# Main_Controller.net
KiCad netlist of a schematic drawn in Altium Designer
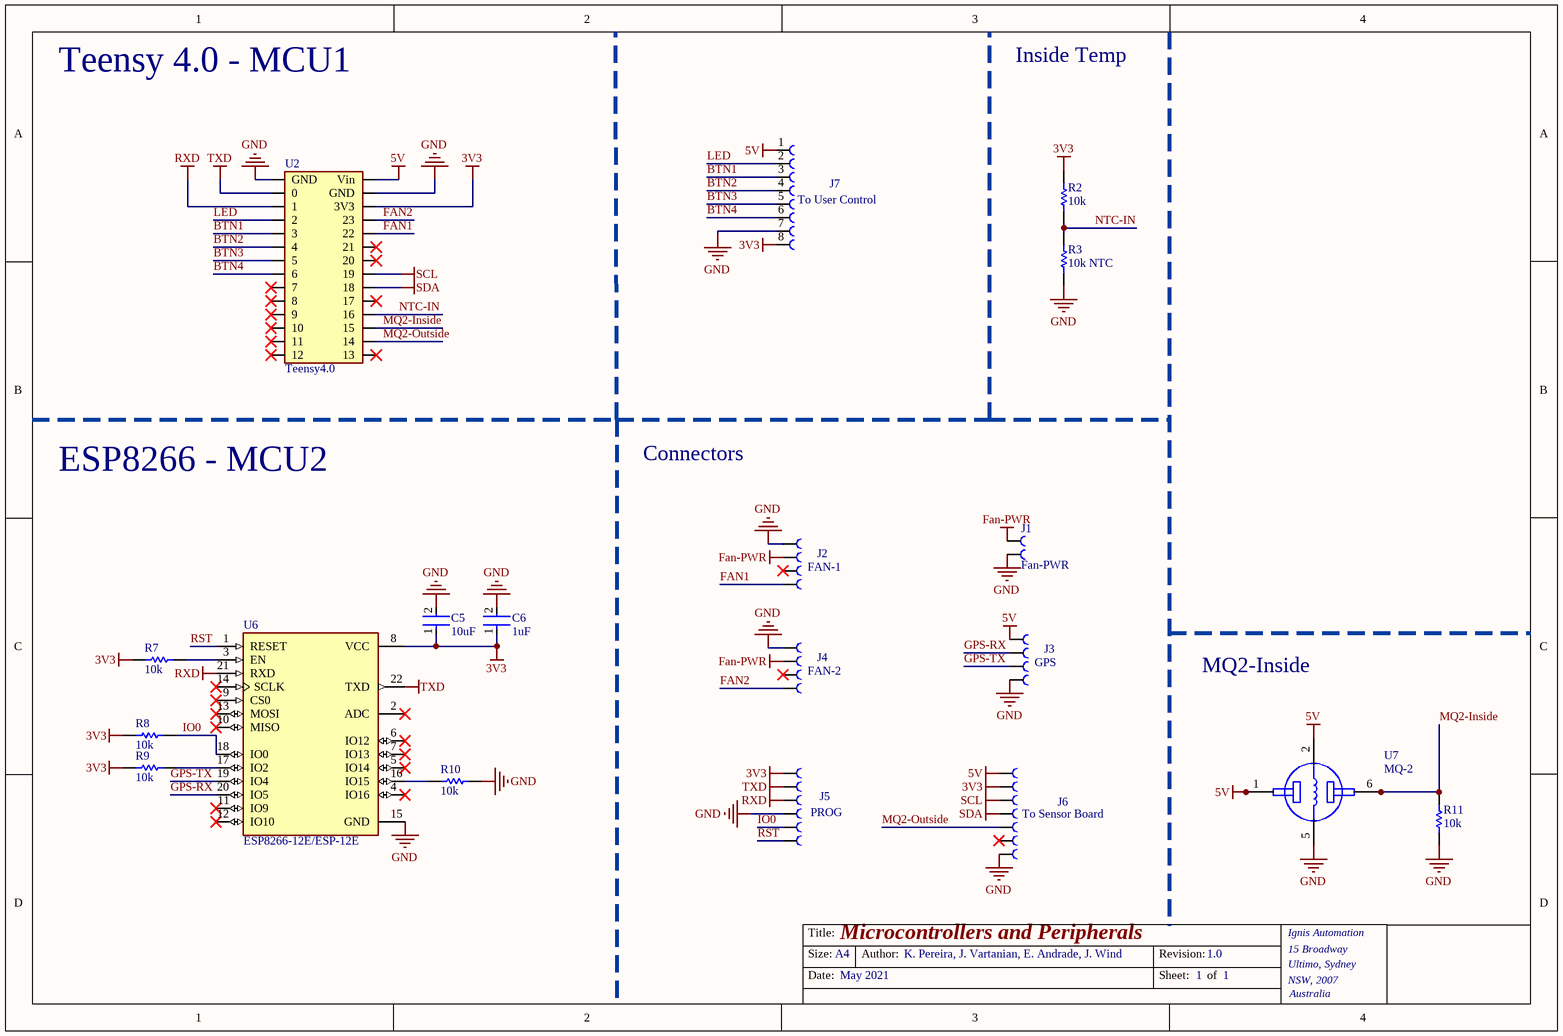
[diagram p0: Main Controller.SchDoc]

(export (version "E")
  (design (tool "Eeschema 10.0.6"))
  (components
    (comp (ref "C5")
      (value "10uF")
      (footprint "FP-CL10-IPC_C")
      (description "CAP CER 10UF 16V X5R 0603")
      (fields (field (name "PART NUMBER") "587-3238-1-ND"))
      (libsource (lib "Altium Content Vault") (part "b4654b650e69147ec39a6b967a45e02"))
    )
    (comp (ref "C6")
      (value "1uF")
      (footprint "FP-CL10-IPC_C")
      (description "CAP CER 1UF 25V X5R 0603")
      (fields (field (name "PART NUMBER") "1276-1102-1-ND"))
      (libsource (lib "Altium Content Vault") (part "b4654b650e69147ec39a6b967a45e02"))
    )
    (comp (ref "J1")
      (value "Fan-PWR")
      (footprint "2pin:61300711821")
      (description "2 Pin")
      (libsource (lib "2pin") (part "61300711821"))
    )
    (comp (ref "J2")
      (value "FAN-1")
      (footprint "4pin:61300711821")
      (description "4 Pin")
      (libsource (lib "4pin") (part "61300711821"))
    )
    (comp (ref "J3")
      (value "GPS")
      (footprint "4pin:61300711821")
      (description "4 Pin")
      (libsource (lib "4pin") (part "61300711821"))
    )
    (comp (ref "J4")
      (value "FAN-2")
      (footprint "4pin:61300711821")
      (description "4 Pin")
      (libsource (lib "4pin") (part "61300711821"))
    )
    (comp (ref "J5")
      (value "PROG")
      (footprint "6pin:61300711821")
      (description "6 Pin")
      (libsource (lib "6pin") (part "61300711821"))
    )
    (comp (ref "J6")
      (value "To Sensor Board")
      (footprint "7pin:61300711821")
      (description "7 Pin")
      (libsource (lib "7pin") (part "61300711821"))
    )
    (comp (ref "J7")
      (value "To User Control")
      (footprint "8pin:61300711821")
      (description "8 Pin")
      (fields (field (name "MF") "WÃ¼rth Elektronik") (field (name "MP") "61300711821"))
      (libsource (lib "8pin") (part "61300711821"))
    )
    (comp (ref "R2")
      (value "10k")
      (footprint "RESC1608X55X30NL15T15")
      (description "RES SMD 10K OHM 1% 1/10W 0603")
      (fields (field (name "PART NUMBER") "A121523CT-ND"))
      (libsource (lib "Altium Content Vault") (part "RES"))
    )
    (comp (ref "R3")
      (value "10k NTC")
      (footprint "RESC1608X55X30NL15T15")
      (description "THERMISTOR NTC 10KOHM 4250K 0603")
      (fields (field (name "PART NUMBER") "P10547CT-ND"))
      (libsource (lib "Altium Content Vault") (part "RES"))
    )
    (comp (ref "R7")
      (value "10k")
      (footprint "RESC1608X55X30NL15T15")
      (description "RES SMD 10K OHM 1% 1/10W 0603")
      (fields (field (name "PART NUMBER") "A121523CT-ND"))
      (libsource (lib "Altium Content Vault") (part "RES"))
    )
    (comp (ref "R8")
      (value "10k")
      (footprint "RESC1608X55X30NL15T15")
      (description "RES SMD 10K OHM 1% 1/10W 0603")
      (fields (field (name "PART NUMBER") "A121523CT-ND"))
      (libsource (lib "Altium Content Vault") (part "RES"))
    )
    (comp (ref "R9")
      (value "10k")
      (footprint "RESC1608X55X30NL15T15")
      (description "RES SMD 10K OHM 1% 1/10W 0603")
      (fields (field (name "PART NUMBER") "A121523CT-ND"))
      (libsource (lib "Altium Content Vault") (part "RES"))
    )
    (comp (ref "R10")
      (value "10k")
      (footprint "RESC1608X55X30NL15T15")
      (description "RES SMD 10K OHM 1% 1/10W 0603")
      (fields (field (name "PART NUMBER") "A121523CT-ND"))
      (libsource (lib "Altium Content Vault") (part "RES"))
    )
    (comp (ref "R11")
      (value "10k")
      (footprint "RESC1608X55X30NL15T15")
      (description "RES SMD 10K OHM 1% 1/10W 0603")
      (fields (field (name "PART NUMBER") "A121523CT-ND"))
      (libsource (lib "Altium Content Vault") (part "RES"))
    )
    (comp (ref "U2")
      (value "Teensy4.0")
      (footprint "Teensy4.0:61301411821")
      (libsource (lib "Teensy4.0") (part "Teensy4.0"))
    )
    (comp (ref "U6")
      (value "ESP8266-12E/ESP-12E")
      (footprint "ESP8266:XCVR_ESP8266-12E/ESP-12E")
      (description "RX TXRX MOD WIFI TRACE ANT SMD")
      (fields (field (name "PART NUMBER") "1528-1438-ND"))
      (libsource (lib "ESP8266") (part "ESP8266-12E/ESP-12E"))
    )
    (comp (ref "U7")
      (value "MQ-2")
      (footprint "MQ-2:XDCR_SEN-08880")
      (description "MQ-2 Gas Sensor")
      (libsource (lib "MQ-2") (part "MQ-2"))
    )
  )
  (nets
    (net (code "1") (name "/BTN1") (class "Default")
      (node (ref "J7") (pin "3") (pinfunction "3_3") (pintype "passive"))
      (node (ref "U2") (pin "5") (pinfunction "3_5") (pintype "passive"))
    )
    (net (code "2") (name "/BTN2") (class "Default")
      (node (ref "J7") (pin "4") (pinfunction "4_4") (pintype "passive"))
      (node (ref "U2") (pin "6") (pinfunction "4_6") (pintype "passive"))
    )
    (net (code "3") (name "/BTN3") (class "Default")
      (node (ref "J7") (pin "5") (pinfunction "5_5") (pintype "passive"))
      (node (ref "U2") (pin "7") (pinfunction "5_7") (pintype "passive"))
    )
    (net (code "4") (name "/BTN4") (class "Default")
      (node (ref "J7") (pin "6") (pinfunction "6_6") (pintype "passive"))
      (node (ref "U2") (pin "8") (pinfunction "6_8") (pintype "passive"))
    )
    (net (code "5") (name "/FAN1") (class "Default")
      (node (ref "J2") (pin "4") (pinfunction "4_4") (pintype "passive"))
      (node (ref "U2") (pin "24") (pinfunction "22_24") (pintype "passive"))
    )
    (net (code "6") (name "/FAN2") (class "Default")
      (node (ref "J4") (pin "4") (pinfunction "4_4") (pintype "passive"))
      (node (ref "U2") (pin "25") (pinfunction "23_25") (pintype "passive"))
    )
    (net (code "7") (name "/GPS-RX") (class "Default")
      (node (ref "J3") (pin "2") (pinfunction "2_2") (pintype "passive"))
      (node (ref "U6") (pin "20") (pinfunction "IO5_20") (pintype "bidirectional"))
    )
    (net (code "8") (name "/GPS-TX") (class "Default")
      (node (ref "J3") (pin "3") (pinfunction "3_3") (pintype "passive"))
      (node (ref "U6") (pin "19") (pinfunction "IO4_19") (pintype "bidirectional"))
    )
    (net (code "9") (name "/IO0") (class "Default")
      (node (ref "J5") (pin "5") (pinfunction "5_5") (pintype "passive"))
      (node (ref "R8") (pin "2") (pinfunction "2_2") (pintype "passive"))
      (node (ref "U6") (pin "18") (pinfunction "IO0_18") (pintype "bidirectional"))
    )
    (net (code "10") (name "/LED") (class "Default")
      (node (ref "J7") (pin "2") (pinfunction "2_2") (pintype "passive"))
      (node (ref "U2") (pin "4") (pinfunction "2_4") (pintype "passive"))
    )
    (net (code "11") (name "/MQ2-Inside") (class "Default")
      (node (ref "R11") (pin "2") (pinfunction "2_2") (pintype "passive"))
      (node (ref "U2") (pin "17") (pinfunction "15_17") (pintype "passive"))
      (node (ref "U7") (pin "4") (pinfunction "B_4") (pintype "passive"))
      (node (ref "U7") (pin "6") (pinfunction "B_6") (pintype "passive"))
    )
    (net (code "12") (name "/MQ2-Outside") (class "Default")
      (node (ref "J6") (pin "5") (pinfunction "5_5") (pintype "passive"))
      (node (ref "U2") (pin "16") (pinfunction "14_16") (pintype "passive"))
    )
    (net (code "13") (name "/NTC-IN") (class "Default")
      (node (ref "R2") (pin "1") (pinfunction "1_1") (pintype "passive"))
      (node (ref "R3") (pin "2") (pinfunction "2_2") (pintype "passive"))
      (node (ref "U2") (pin "18") (pinfunction "16_18") (pintype "passive"))
    )
    (net (code "14") (name "/RST") (class "Default")
      (node (ref "J5") (pin "6") (pinfunction "6_6") (pintype "passive"))
      (node (ref "U6") (pin "1") (pinfunction "RESET_1") (pintype "input"))
    )
    (net (code "15") (name "3V3") (class "Default")
      (node (ref "C5") (pin "1") (pinfunction "1_1") (pintype "passive"))
      (node (ref "C6") (pin "1") (pinfunction "1_1") (pintype "passive"))
      (node (ref "J5") (pin "1") (pinfunction "1_1") (pintype "passive"))
      (node (ref "J6") (pin "2") (pinfunction "2_2") (pintype "passive"))
      (node (ref "J7") (pin "8") (pinfunction "8_8") (pintype "passive"))
      (node (ref "R2") (pin "2") (pinfunction "2_2") (pintype "passive"))
      (node (ref "R7") (pin "1") (pinfunction "1_1") (pintype "passive"))
      (node (ref "R8") (pin "1") (pinfunction "1_1") (pintype "passive"))
      (node (ref "R9") (pin "1") (pinfunction "1_1") (pintype "passive"))
      (node (ref "U2") (pin "26") (pinfunction "3V3_26") (pintype "passive"))
      (node (ref "U6") (pin "8") (pinfunction "VCC_8") (pintype "power_in"))
    )
    (net (code "16") (name "5V") (class "Default")
      (node (ref "J3") (pin "1") (pinfunction "1_1") (pintype "passive"))
      (node (ref "J6") (pin "1") (pinfunction "1_1") (pintype "passive"))
      (node (ref "J7") (pin "1") (pinfunction "1_1") (pintype "passive"))
      (node (ref "U2") (pin "28") (pinfunction "Vin_28") (pintype "passive"))
      (node (ref "U7") (pin "1") (pinfunction "A_1") (pintype "passive"))
      (node (ref "U7") (pin "2") (pinfunction "H1_2") (pintype "passive"))
      (node (ref "U7") (pin "3") (pinfunction "A_3") (pintype "passive"))
    )
    (net (code "17") (name "Fan-PWR") (class "Default")
      (node (ref "J1") (pin "2") (pinfunction "2_2") (pintype "passive"))
      (node (ref "J2") (pin "2") (pinfunction "2_2") (pintype "passive"))
      (node (ref "J4") (pin "2") (pinfunction "2_2") (pintype "passive"))
    )
    (net (code "18") (name "GND") (class "Default")
      (node (ref "C5") (pin "2") (pinfunction "2_2") (pintype "passive"))
      (node (ref "C6") (pin "2") (pinfunction "2_2") (pintype "passive"))
      (node (ref "J1") (pin "1") (pinfunction "1_1") (pintype "passive"))
      (node (ref "J2") (pin "1") (pinfunction "1_1") (pintype "passive"))
      (node (ref "J3") (pin "4") (pinfunction "4_4") (pintype "passive"))
      (node (ref "J4") (pin "1") (pinfunction "1_1") (pintype "passive"))
      (node (ref "J5") (pin "4") (pinfunction "4_4") (pintype "passive"))
      (node (ref "J6") (pin "7") (pinfunction "7_7") (pintype "passive"))
      (node (ref "J7") (pin "7") (pinfunction "7_7") (pintype "passive"))
      (node (ref "R10") (pin "2") (pinfunction "2_2") (pintype "passive"))
      (node (ref "R11") (pin "1") (pinfunction "1_1") (pintype "passive"))
      (node (ref "R3") (pin "1") (pinfunction "1_1") (pintype "passive"))
      (node (ref "U2") (pin "1") (pinfunction "GND_1") (pintype "passive"))
      (node (ref "U2") (pin "27") (pinfunction "GND_27") (pintype "passive"))
      (node (ref "U6") (pin "15") (pinfunction "GND_15") (pintype "power_in"))
      (node (ref "U7") (pin "5") (pinfunction "H2_5") (pintype "passive"))
    )
    (net (code "19") (name "Net-(U6-EN)") (class "Default")
      (node (ref "R7") (pin "2") (pinfunction "2_2") (pintype "passive"))
      (node (ref "U6") (pin "3") (pinfunction "EN_3") (pintype "input"))
    )
    (net (code "20") (name "Net-(U6-IO2)") (class "Default")
      (node (ref "R9") (pin "2") (pinfunction "2_2") (pintype "passive"))
      (node (ref "U6") (pin "17") (pinfunction "IO2_17") (pintype "bidirectional"))
    )
    (net (code "21") (name "Net-(U6-IO15)") (class "Default")
      (node (ref "R10") (pin "1") (pinfunction "1_1") (pintype "passive"))
      (node (ref "U6") (pin "16") (pinfunction "IO15_16") (pintype "bidirectional"))
    )
    (net (code "22") (name "RXD") (class "Default")
      (node (ref "J5") (pin "3") (pinfunction "3_3") (pintype "passive"))
      (node (ref "U2") (pin "3") (pinfunction "1_3") (pintype "passive"))
      (node (ref "U6") (pin "21") (pinfunction "RXD_21") (pintype "input"))
    )
    (net (code "23") (name "SCL") (class "Default")
      (node (ref "J6") (pin "3") (pinfunction "3_3") (pintype "passive"))
      (node (ref "U2") (pin "21") (pinfunction "19_21") (pintype "passive"))
    )
    (net (code "24") (name "SDA") (class "Default")
      (node (ref "J6") (pin "4") (pinfunction "4_4") (pintype "passive"))
      (node (ref "U2") (pin "20") (pinfunction "18_20") (pintype "passive"))
    )
    (net (code "25") (name "TXD") (class "Default")
      (node (ref "J5") (pin "2") (pinfunction "2_2") (pintype "passive"))
      (node (ref "U2") (pin "2") (pinfunction "0_2") (pintype "passive"))
      (node (ref "U6") (pin "22") (pinfunction "TXD_22") (pintype "output"))
    )
    (net (code "26") (name "unconnected-(J2-Pad3)") (class "Default")
      (node (ref "J2") (pin "3") (pinfunction "3_3") (pintype "passive+no_connect"))
    )
    (net (code "27") (name "unconnected-(J4-Pad3)") (class "Default")
      (node (ref "J4") (pin "3") (pinfunction "3_3") (pintype "passive+no_connect"))
    )
    (net (code "28") (name "unconnected-(J6-Pad6)") (class "Default")
      (node (ref "J6") (pin "6") (pinfunction "6_6") (pintype "passive+no_connect"))
    )
    (net (code "29") (name "unconnected-(U2-7-Pad9)") (class "Default")
      (node (ref "U2") (pin "9") (pinfunction "7_9") (pintype "passive+no_connect"))
    )
    (net (code "30") (name "unconnected-(U2-8-Pad10)") (class "Default")
      (node (ref "U2") (pin "10") (pinfunction "8_10") (pintype "passive+no_connect"))
    )
    (net (code "31") (name "unconnected-(U2-9-Pad11)") (class "Default")
      (node (ref "U2") (pin "11") (pinfunction "9_11") (pintype "passive+no_connect"))
    )
    (net (code "32") (name "unconnected-(U2-10-Pad12)") (class "Default")
      (node (ref "U2") (pin "12") (pinfunction "10_12") (pintype "passive+no_connect"))
    )
    (net (code "33") (name "unconnected-(U2-11-Pad13)") (class "Default")
      (node (ref "U2") (pin "13") (pinfunction "11_13") (pintype "passive+no_connect"))
    )
    (net (code "34") (name "unconnected-(U2-12-Pad14)") (class "Default")
      (node (ref "U2") (pin "14") (pinfunction "12_14") (pintype "passive+no_connect"))
    )
    (net (code "35") (name "unconnected-(U2-13-Pad15)") (class "Default")
      (node (ref "U2") (pin "15") (pinfunction "13_15") (pintype "passive+no_connect"))
    )
    (net (code "36") (name "unconnected-(U2-17-Pad19)") (class "Default")
      (node (ref "U2") (pin "19") (pinfunction "17_19") (pintype "passive+no_connect"))
    )
    (net (code "37") (name "unconnected-(U2-20-Pad22)") (class "Default")
      (node (ref "U2") (pin "22") (pinfunction "20_22") (pintype "passive+no_connect"))
    )
    (net (code "38") (name "unconnected-(U2-21-Pad23)") (class "Default")
      (node (ref "U2") (pin "23") (pinfunction "21_23") (pintype "passive+no_connect"))
    )
    (net (code "39") (name "unconnected-(U6-ADC-Pad2)") (class "Default")
      (node (ref "U6") (pin "2") (pinfunction "ADC_2") (pintype "passive+no_connect"))
    )
    (net (code "40") (name "unconnected-(U6-CS0-Pad9)") (class "Default")
      (node (ref "U6") (pin "9") (pinfunction "CS0_9") (pintype "input+no_connect"))
    )
    (net (code "41") (name "unconnected-(U6-IO9-Pad11)") (class "Default")
      (node (ref "U6") (pin "11") (pinfunction "IO9_11") (pintype "bidirectional+no_connect"))
    )
    (net (code "42") (name "unconnected-(U6-IO10-Pad12)") (class "Default")
      (node (ref "U6") (pin "12") (pinfunction "IO10_12") (pintype "bidirectional+no_connect"))
    )
    (net (code "43") (name "unconnected-(U6-IO12-Pad6)") (class "Default")
      (node (ref "U6") (pin "6") (pinfunction "IO12_6") (pintype "bidirectional+no_connect"))
    )
    (net (code "44") (name "unconnected-(U6-IO13-Pad7)") (class "Default")
      (node (ref "U6") (pin "7") (pinfunction "IO13_7") (pintype "bidirectional+no_connect"))
    )
    (net (code "45") (name "unconnected-(U6-IO14-Pad5)") (class "Default")
      (node (ref "U6") (pin "5") (pinfunction "IO14_5") (pintype "bidirectional+no_connect"))
    )
    (net (code "46") (name "unconnected-(U6-IO16-Pad4)") (class "Default")
      (node (ref "U6") (pin "4") (pinfunction "IO16_4") (pintype "bidirectional+no_connect"))
    )
    (net (code "47") (name "unconnected-(U6-MISO-Pad10)") (class "Default")
      (node (ref "U6") (pin "10") (pinfunction "MISO_10") (pintype "bidirectional+no_connect"))
    )
    (net (code "48") (name "unconnected-(U6-MOSI-Pad13)") (class "Default")
      (node (ref "U6") (pin "13") (pinfunction "MOSI_13") (pintype "bidirectional+no_connect"))
    )
    (net (code "49") (name "unconnected-(U6-SCLK-Pad14)") (class "Default")
      (node (ref "U6") (pin "14") (pinfunction "SCLK_14") (pintype "input+no_connect"))
    )
  )
)
